# G021old.net
KiCad netlist of a schematic drawn in EAGLE
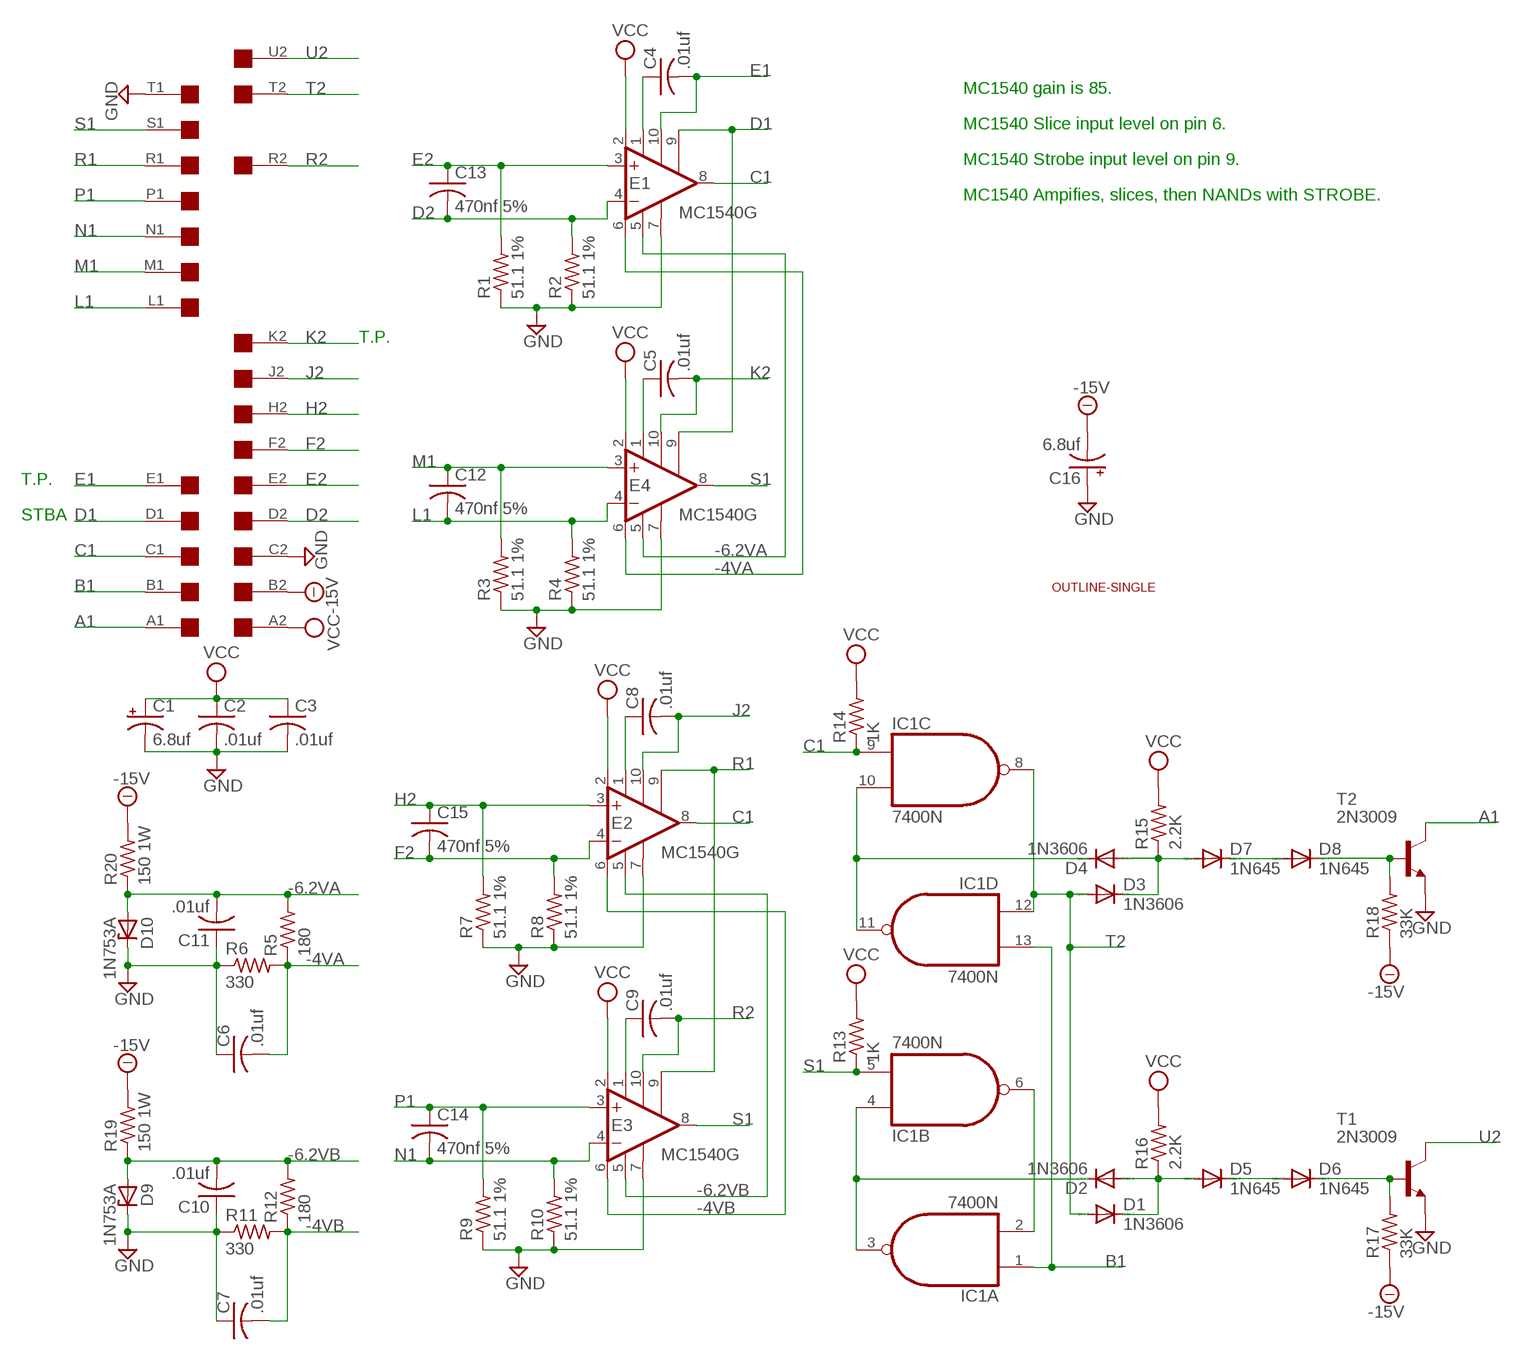
[diagram p0: schematic, sheet 1]

(export (version "E")
  (design (tool "Eeschema 10.0.6"))
  (components
    (comp (ref "C1")
      (value "6.8uf")
      (footprint "eagle-import:E15-5")
      (libsource (lib "eagle-import") (part "CPOL-USE15-5AXIAL"))
    )
    (comp (ref "C2")
      (value ".01uf")
      (footprint "eagle-import:C050-025X075")
      (libsource (lib "eagle-import") (part "C-US050-025X075"))
    )
    (comp (ref "C3")
      (value ".01uf")
      (footprint "eagle-import:C050-025X075")
      (libsource (lib "eagle-import") (part "C-US050-025X075"))
    )
    (comp (ref "C4")
      (value ".01uf")
      (footprint "eagle-import:C050-025X075")
      (libsource (lib "eagle-import") (part "C-US050-025X075"))
    )
    (comp (ref "C5")
      (value ".01uf")
      (footprint "eagle-import:C050-025X075")
      (libsource (lib "eagle-import") (part "C-US050-025X075"))
    )
    (comp (ref "C6")
      (value ".01uf")
      (footprint "eagle-import:C050-025X075")
      (libsource (lib "eagle-import") (part "C-US050-025X075"))
    )
    (comp (ref "C7")
      (value ".01uf")
      (footprint "eagle-import:C050-025X075")
      (libsource (lib "eagle-import") (part "C-US050-025X075"))
    )
    (comp (ref "C8")
      (value ".01uf")
      (footprint "eagle-import:C050-025X075")
      (libsource (lib "eagle-import") (part "C-US050-025X075"))
    )
    (comp (ref "C9")
      (value ".01uf")
      (footprint "eagle-import:C050-025X075")
      (libsource (lib "eagle-import") (part "C-US050-025X075"))
    )
    (comp (ref "C10")
      (value ".01uf")
      (footprint "eagle-import:C050-025X075")
      (libsource (lib "eagle-import") (part "C-US050-025X075"))
    )
    (comp (ref "C11")
      (value ".01uf")
      (footprint "eagle-import:C050-025X075")
      (libsource (lib "eagle-import") (part "C-US050-025X075"))
    )
    (comp (ref "C12")
      (value "470nf 5%")
      (footprint "eagle-import:C050-025X075")
      (libsource (lib "eagle-import") (part "C-US050-025X075"))
    )
    (comp (ref "C13")
      (value "470nf 5%")
      (footprint "eagle-import:C050-025X075")
      (libsource (lib "eagle-import") (part "C-US050-025X075"))
    )
    (comp (ref "C14")
      (value "470nf 5%")
      (footprint "eagle-import:C050-025X075")
      (libsource (lib "eagle-import") (part "C-US050-025X075"))
    )
    (comp (ref "C15")
      (value "470nf 5%")
      (footprint "eagle-import:C050-025X075")
      (libsource (lib "eagle-import") (part "C-US050-025X075"))
    )
    (comp (ref "C16")
      (value "6.8uf")
      (footprint "eagle-import:E15-5")
      (libsource (lib "eagle-import") (part "CPOL-USE15-5AXIAL"))
    )
    (comp (ref "D1")
      (value "1N3606")
      (footprint "eagle-import:DO35-10")
      (libsource (lib "eagle-import") (part "1N4148DO35-10"))
    )
    (comp (ref "D2")
      (value "1N3606")
      (footprint "eagle-import:DO35-10")
      (libsource (lib "eagle-import") (part "1N4148DO35-10"))
    )
    (comp (ref "D3")
      (value "1N3606")
      (footprint "eagle-import:DO35-10")
      (libsource (lib "eagle-import") (part "1N4148DO35-10"))
    )
    (comp (ref "D4")
      (value "1N3606")
      (footprint "eagle-import:DO35-10")
      (libsource (lib "eagle-import") (part "1N4148DO35-10"))
    )
    (comp (ref "D5")
      (value "1N645")
      (footprint "eagle-import:DO35-10")
      (libsource (lib "eagle-import") (part "1N4148DO35-10"))
    )
    (comp (ref "D6")
      (value "1N645")
      (footprint "eagle-import:DO35-10")
      (libsource (lib "eagle-import") (part "1N4148DO35-10"))
    )
    (comp (ref "D7")
      (value "1N645")
      (footprint "eagle-import:DO35-10")
      (libsource (lib "eagle-import") (part "1N4148DO35-10"))
    )
    (comp (ref "D8")
      (value "1N645")
      (footprint "eagle-import:DO35-10")
      (libsource (lib "eagle-import") (part "1N4148DO35-10"))
    )
    (comp (ref "D9")
      (value "1N753A")
      (footprint "eagle-import:F126Z10")
      (libsource (lib "eagle-import") (part "ZENER-DIODEF126-10"))
    )
    (comp (ref "D10")
      (value "1N753A")
      (footprint "eagle-import:F126Z10")
      (libsource (lib "eagle-import") (part "ZENER-DIODEF126-10"))
    )
    (comp (ref "E1")
      (value "MC1540G")
      (footprint "eagle-import:602B")
      (libsource (lib "eagle-import") (part "MC1540G"))
    )
    (comp (ref "E2")
      (value "MC1540G")
      (footprint "eagle-import:602B")
      (libsource (lib "eagle-import") (part "MC1540G"))
    )
    (comp (ref "E3")
      (value "MC1540G")
      (footprint "eagle-import:602B")
      (libsource (lib "eagle-import") (part "MC1540G"))
    )
    (comp (ref "E4")
      (value "MC1540G")
      (footprint "eagle-import:602B")
      (libsource (lib "eagle-import") (part "MC1540G"))
    )
    (comp (ref "IC1")
      (value "7400N")
      (footprint "eagle-import:DIL14")
      (libsource (lib "eagle-import") (part "7400N"))
    )
    (comp (ref "R1")
      (value "51.1 1%")
      (footprint "eagle-import:0207_10")
      (libsource (lib "eagle-import") (part "R-US_0207/10"))
    )
    (comp (ref "R2")
      (value "51.1 1%")
      (footprint "eagle-import:0207_10")
      (libsource (lib "eagle-import") (part "R-US_0207/10"))
    )
    (comp (ref "R3")
      (value "51.1 1%")
      (footprint "eagle-import:0207_10")
      (libsource (lib "eagle-import") (part "R-US_0207/10"))
    )
    (comp (ref "R4")
      (value "51.1 1%")
      (footprint "eagle-import:0207_10")
      (libsource (lib "eagle-import") (part "R-US_0207/10"))
    )
    (comp (ref "R5")
      (value "180")
      (footprint "eagle-import:0207_10")
      (libsource (lib "eagle-import") (part "R-US_0207/10"))
    )
    (comp (ref "R6")
      (value "330")
      (footprint "eagle-import:0207_10")
      (libsource (lib "eagle-import") (part "R-US_0207/10"))
    )
    (comp (ref "R7")
      (value "51.1 1%")
      (footprint "eagle-import:0207_10")
      (libsource (lib "eagle-import") (part "R-US_0207/10"))
    )
    (comp (ref "R8")
      (value "51.1 1%")
      (footprint "eagle-import:0207_10")
      (libsource (lib "eagle-import") (part "R-US_0207/10"))
    )
    (comp (ref "R9")
      (value "51.1 1%")
      (footprint "eagle-import:0207_10")
      (libsource (lib "eagle-import") (part "R-US_0207/10"))
    )
    (comp (ref "R10")
      (value "51.1 1%")
      (footprint "eagle-import:0207_10")
      (libsource (lib "eagle-import") (part "R-US_0207/10"))
    )
    (comp (ref "R11")
      (value "330")
      (footprint "eagle-import:0207_10")
      (libsource (lib "eagle-import") (part "R-US_0207/10"))
    )
    (comp (ref "R12")
      (value "180")
      (footprint "eagle-import:0207_10")
      (libsource (lib "eagle-import") (part "R-US_0207/10"))
    )
    (comp (ref "R13")
      (value "1K")
      (footprint "eagle-import:0207_10")
      (libsource (lib "eagle-import") (part "R-US_0207/10"))
    )
    (comp (ref "R14")
      (value "1K")
      (footprint "eagle-import:0207_10")
      (libsource (lib "eagle-import") (part "R-US_0207/10"))
    )
    (comp (ref "R15")
      (value "2.2K")
      (footprint "eagle-import:0207_10")
      (libsource (lib "eagle-import") (part "R-US_0207/10"))
    )
    (comp (ref "R16")
      (value "2.2K")
      (footprint "eagle-import:0207_10")
      (libsource (lib "eagle-import") (part "R-US_0207/10"))
    )
    (comp (ref "R17")
      (value "33K")
      (footprint "eagle-import:0207_10")
      (libsource (lib "eagle-import") (part "R-US_0207/10"))
    )
    (comp (ref "R18")
      (value "33K")
      (footprint "eagle-import:0207_10")
      (libsource (lib "eagle-import") (part "R-US_0207/10"))
    )
    (comp (ref "R19")
      (value "150 1W")
      (footprint "eagle-import:0414_15")
      (libsource (lib "eagle-import") (part "R-US_0414/15"))
    )
    (comp (ref "R20")
      (value "150 1W")
      (footprint "eagle-import:0414_15")
      (libsource (lib "eagle-import") (part "R-US_0414/15"))
    )
    (comp (ref "T1")
      (value "2N3009")
      (footprint "eagle-import:TO92")
      (libsource (lib "eagle-import") (part "2N3565"))
    )
    (comp (ref "T2")
      (value "2N3009")
      (footprint "eagle-import:TO92")
      (libsource (lib "eagle-import") (part "2N3565"))
    )
    (comp (ref "U$1")
      (value "SINGLE")
      (footprint "eagle-import:EDGE-CON2")
      (libsource (lib "eagle-import") (part "SINGLE"))
    )
    (comp (ref "U$2")
      (value "OUTLINE-SINGLE")
      (footprint "eagle-import:SINGLE")
      (libsource (lib "eagle-import") (part "OUTLINE-SINGLE"))
    )
  )
  (nets
    (net (code "1") (name "-15V") (class "Default")
      (node (ref "C16") (pin "-") (pinfunction "-_-") (pintype "passive"))
      (node (ref "R17") (pin "1") (pinfunction "1_1") (pintype "passive"))
      (node (ref "R18") (pin "1") (pinfunction "1_1") (pintype "passive"))
      (node (ref "R19") (pin "2") (pinfunction "2_2") (pintype "passive"))
      (node (ref "R20") (pin "2") (pinfunction "2_2") (pintype "passive"))
      (node (ref "U$1") (pin "B2") (pinfunction "1_B2") (pintype "bidirectional"))
    )
    (net (code "2") (name "/-4VA") (class "Default")
      (node (ref "C6") (pin "2") (pinfunction "2_2") (pintype "passive"))
      (node (ref "E1") (pin "6") (pinfunction "SLICE_6") (pintype "bidirectional"))
      (node (ref "E4") (pin "6") (pinfunction "SLICE_6") (pintype "bidirectional"))
      (node (ref "R5") (pin "1") (pinfunction "1_1") (pintype "passive"))
      (node (ref "R6") (pin "2") (pinfunction "2_2") (pintype "passive"))
    )
    (net (code "3") (name "/-4VB") (class "Default")
      (node (ref "C7") (pin "2") (pinfunction "2_2") (pintype "passive"))
      (node (ref "E2") (pin "6") (pinfunction "SLICE_6") (pintype "bidirectional"))
      (node (ref "E3") (pin "6") (pinfunction "SLICE_6") (pintype "bidirectional"))
      (node (ref "R11") (pin "2") (pinfunction "2_2") (pintype "passive"))
      (node (ref "R12") (pin "1") (pinfunction "1_1") (pintype "passive"))
    )
    (net (code "4") (name "/-6.2VA") (class "Default")
      (node (ref "C11") (pin "2") (pinfunction "2_2") (pintype "passive"))
      (node (ref "D10") (pin "A") (pinfunction "A_A") (pintype "passive"))
      (node (ref "E1") (pin "5") (pinfunction "V-_5") (pintype "power_in"))
      (node (ref "E4") (pin "5") (pinfunction "V-_5") (pintype "power_in"))
      (node (ref "R20") (pin "1") (pinfunction "1_1") (pintype "passive"))
      (node (ref "R5") (pin "2") (pinfunction "2_2") (pintype "passive"))
    )
    (net (code "5") (name "/-6.2VB") (class "Default")
      (node (ref "C10") (pin "2") (pinfunction "2_2") (pintype "passive"))
      (node (ref "D9") (pin "A") (pinfunction "A_A") (pintype "passive"))
      (node (ref "E2") (pin "5") (pinfunction "V-_5") (pintype "power_in"))
      (node (ref "E3") (pin "5") (pinfunction "V-_5") (pintype "power_in"))
      (node (ref "R12") (pin "2") (pinfunction "2_2") (pintype "passive"))
      (node (ref "R19") (pin "1") (pinfunction "1_1") (pintype "passive"))
    )
    (net (code "6") (name "/A1") (class "Default")
      (node (ref "T2") (pin "1") (pinfunction "C_1") (pintype "passive"))
      (node (ref "U$1") (pin "A1") (pinfunction "1_A1") (pintype "bidirectional"))
    )
    (net (code "7") (name "/B1") (class "Default")
      (node (ref "IC1") (pin "1") (pinfunction "I0_1") (pintype "input"))
      (node (ref "IC1") (pin "13") (pinfunction "I1_13") (pintype "input"))
      (node (ref "U$1") (pin "B1") (pinfunction "1_B1") (pintype "bidirectional"))
    )
    (net (code "8") (name "/C1") (class "Default")
      (node (ref "E1") (pin "8") (pinfunction "OUT_8") (pintype "open_collector"))
      (node (ref "E2") (pin "8") (pinfunction "OUT_8") (pintype "open_collector"))
      (node (ref "IC1") (pin "9") (pinfunction "I0_9") (pintype "input"))
      (node (ref "R14") (pin "1") (pinfunction "1_1") (pintype "passive"))
      (node (ref "U$1") (pin "C1") (pinfunction "1_C1") (pintype "bidirectional"))
    )
    (net (code "9") (name "/D1") (class "Default")
      (node (ref "E1") (pin "9") (pinfunction "ISTROBE_9") (pintype "passive"))
      (node (ref "E4") (pin "9") (pinfunction "ISTROBE_9") (pintype "passive"))
      (node (ref "U$1") (pin "D1") (pinfunction "1_D1") (pintype "bidirectional"))
    )
    (net (code "10") (name "/D2") (class "Default")
      (node (ref "C13") (pin "2") (pinfunction "2_2") (pintype "passive"))
      (node (ref "E1") (pin "4") (pinfunction "-IN_4") (pintype "input"))
      (node (ref "R2") (pin "2") (pinfunction "2_2") (pintype "passive"))
      (node (ref "U$1") (pin "D2") (pinfunction "1_D2") (pintype "bidirectional"))
    )
    (net (code "11") (name "/E1") (class "Default")
      (node (ref "C4") (pin "2") (pinfunction "2_2") (pintype "passive"))
      (node (ref "E1") (pin "10") (pinfunction "CEXTB_10") (pintype "passive"))
      (node (ref "U$1") (pin "E1") (pinfunction "1_E1") (pintype "bidirectional"))
    )
    (net (code "12") (name "/E2") (class "Default")
      (node (ref "C13") (pin "1") (pinfunction "1_1") (pintype "passive"))
      (node (ref "E1") (pin "3") (pinfunction "+IN_3") (pintype "input"))
      (node (ref "R1") (pin "2") (pinfunction "2_2") (pintype "passive"))
      (node (ref "U$1") (pin "E2") (pinfunction "1_E2") (pintype "bidirectional"))
    )
    (net (code "13") (name "/F2") (class "Default")
      (node (ref "C15") (pin "2") (pinfunction "2_2") (pintype "passive"))
      (node (ref "E2") (pin "4") (pinfunction "-IN_4") (pintype "input"))
      (node (ref "R8") (pin "2") (pinfunction "2_2") (pintype "passive"))
      (node (ref "U$1") (pin "F2") (pinfunction "1_F2") (pintype "bidirectional"))
    )
    (net (code "14") (name "/H2") (class "Default")
      (node (ref "C15") (pin "1") (pinfunction "1_1") (pintype "passive"))
      (node (ref "E2") (pin "3") (pinfunction "+IN_3") (pintype "input"))
      (node (ref "R7") (pin "2") (pinfunction "2_2") (pintype "passive"))
      (node (ref "U$1") (pin "H2") (pinfunction "1_H2") (pintype "bidirectional"))
    )
    (net (code "15") (name "/J2") (class "Default")
      (node (ref "C8") (pin "2") (pinfunction "2_2") (pintype "passive"))
      (node (ref "E2") (pin "10") (pinfunction "CEXTB_10") (pintype "passive"))
      (node (ref "U$1") (pin "J2") (pinfunction "1_J2") (pintype "bidirectional"))
    )
    (net (code "16") (name "/K2") (class "Default")
      (node (ref "C5") (pin "2") (pinfunction "2_2") (pintype "passive"))
      (node (ref "E4") (pin "10") (pinfunction "CEXTB_10") (pintype "passive"))
      (node (ref "U$1") (pin "K2") (pinfunction "1_K2") (pintype "bidirectional"))
    )
    (net (code "17") (name "/L1") (class "Default")
      (node (ref "C12") (pin "2") (pinfunction "2_2") (pintype "passive"))
      (node (ref "E4") (pin "4") (pinfunction "-IN_4") (pintype "input"))
      (node (ref "R4") (pin "2") (pinfunction "2_2") (pintype "passive"))
      (node (ref "U$1") (pin "L1") (pinfunction "1_L1") (pintype "bidirectional"))
    )
    (net (code "18") (name "/M1") (class "Default")
      (node (ref "C12") (pin "1") (pinfunction "1_1") (pintype "passive"))
      (node (ref "E4") (pin "3") (pinfunction "+IN_3") (pintype "input"))
      (node (ref "R3") (pin "2") (pinfunction "2_2") (pintype "passive"))
      (node (ref "U$1") (pin "M1") (pinfunction "1_M1") (pintype "bidirectional"))
    )
    (net (code "19") (name "/N1") (class "Default")
      (node (ref "C14") (pin "2") (pinfunction "2_2") (pintype "passive"))
      (node (ref "E3") (pin "4") (pinfunction "-IN_4") (pintype "input"))
      (node (ref "R10") (pin "2") (pinfunction "2_2") (pintype "passive"))
      (node (ref "U$1") (pin "N1") (pinfunction "1_N1") (pintype "bidirectional"))
    )
    (net (code "20") (name "/P1") (class "Default")
      (node (ref "C14") (pin "1") (pinfunction "1_1") (pintype "passive"))
      (node (ref "E3") (pin "3") (pinfunction "+IN_3") (pintype "input"))
      (node (ref "R9") (pin "2") (pinfunction "2_2") (pintype "passive"))
      (node (ref "U$1") (pin "P1") (pinfunction "1_P1") (pintype "bidirectional"))
    )
    (net (code "21") (name "/R1") (class "Default")
      (node (ref "E2") (pin "9") (pinfunction "ISTROBE_9") (pintype "passive"))
      (node (ref "E3") (pin "9") (pinfunction "ISTROBE_9") (pintype "passive"))
      (node (ref "U$1") (pin "R1") (pinfunction "1_R1") (pintype "bidirectional"))
    )
    (net (code "22") (name "/R2") (class "Default")
      (node (ref "C9") (pin "2") (pinfunction "2_2") (pintype "passive"))
      (node (ref "E3") (pin "10") (pinfunction "CEXTB_10") (pintype "passive"))
      (node (ref "U$1") (pin "R2") (pinfunction "1_R2") (pintype "bidirectional"))
    )
    (net (code "23") (name "/S1") (class "Default")
      (node (ref "E3") (pin "8") (pinfunction "OUT_8") (pintype "open_collector"))
      (node (ref "E4") (pin "8") (pinfunction "OUT_8") (pintype "open_collector"))
      (node (ref "IC1") (pin "5") (pinfunction "I1_5") (pintype "input"))
      (node (ref "R13") (pin "1") (pinfunction "1_1") (pintype "passive"))
      (node (ref "U$1") (pin "S1") (pinfunction "1_S1") (pintype "bidirectional"))
    )
    (net (code "24") (name "/T2") (class "Default")
      (node (ref "D1") (pin "A") (pinfunction "A_A") (pintype "passive"))
      (node (ref "D3") (pin "A") (pinfunction "A_A") (pintype "passive"))
      (node (ref "IC1") (pin "12") (pinfunction "I0_12") (pintype "input"))
      (node (ref "IC1") (pin "8") (pinfunction "O_8") (pintype "output"))
      (node (ref "U$1") (pin "T2") (pinfunction "1_T2") (pintype "bidirectional"))
    )
    (net (code "25") (name "/U2") (class "Default")
      (node (ref "T1") (pin "1") (pinfunction "C_1") (pintype "passive"))
      (node (ref "U$1") (pin "U2") (pinfunction "1_U2") (pintype "bidirectional"))
    )
    (net (code "26") (name "GND") (class "Default")
      (node (ref "C1") (pin "-") (pinfunction "-_-") (pintype "passive"))
      (node (ref "C10") (pin "1") (pinfunction "1_1") (pintype "passive"))
      (node (ref "C11") (pin "1") (pinfunction "1_1") (pintype "passive"))
      (node (ref "C16") (pin "+") (pinfunction "+_+") (pintype "passive"))
      (node (ref "C2") (pin "2") (pinfunction "2_2") (pintype "passive"))
      (node (ref "C3") (pin "2") (pinfunction "2_2") (pintype "passive"))
      (node (ref "C6") (pin "1") (pinfunction "1_1") (pintype "passive"))
      (node (ref "C7") (pin "1") (pinfunction "1_1") (pintype "passive"))
      (node (ref "D10") (pin "C") (pinfunction "C_C") (pintype "passive"))
      (node (ref "D9") (pin "C") (pinfunction "C_C") (pintype "passive"))
      (node (ref "E1") (pin "7") (pinfunction "GND_7") (pintype "power_in"))
      (node (ref "E2") (pin "7") (pinfunction "GND_7") (pintype "power_in"))
      (node (ref "E3") (pin "7") (pinfunction "GND_7") (pintype "power_in"))
      (node (ref "E4") (pin "7") (pinfunction "GND_7") (pintype "power_in"))
      (node (ref "R1") (pin "1") (pinfunction "1_1") (pintype "passive"))
      (node (ref "R10") (pin "1") (pinfunction "1_1") (pintype "passive"))
      (node (ref "R11") (pin "1") (pinfunction "1_1") (pintype "passive"))
      (node (ref "R2") (pin "1") (pinfunction "1_1") (pintype "passive"))
      (node (ref "R3") (pin "1") (pinfunction "1_1") (pintype "passive"))
      (node (ref "R4") (pin "1") (pinfunction "1_1") (pintype "passive"))
      (node (ref "R6") (pin "1") (pinfunction "1_1") (pintype "passive"))
      (node (ref "R7") (pin "1") (pinfunction "1_1") (pintype "passive"))
      (node (ref "R8") (pin "1") (pinfunction "1_1") (pintype "passive"))
      (node (ref "R9") (pin "1") (pinfunction "1_1") (pintype "passive"))
      (node (ref "T1") (pin "3") (pinfunction "E_3") (pintype "passive"))
      (node (ref "T2") (pin "3") (pinfunction "E_3") (pintype "passive"))
      (node (ref "U$1") (pin "C2") (pinfunction "1_C2") (pintype "bidirectional"))
      (node (ref "U$1") (pin "T1") (pinfunction "1_T1") (pintype "bidirectional"))
    )
    (net (code "27") (name "Net-(D1-PadC)") (class "Default")
      (node (ref "D1") (pin "C") (pinfunction "C_C") (pintype "passive"))
      (node (ref "D2") (pin "A") (pinfunction "A_A") (pintype "passive"))
      (node (ref "D5") (pin "A") (pinfunction "A_A") (pintype "passive"))
      (node (ref "R16") (pin "1") (pinfunction "1_1") (pintype "passive"))
    )
    (net (code "28") (name "Net-(D3-PadC)") (class "Default")
      (node (ref "D3") (pin "C") (pinfunction "C_C") (pintype "passive"))
      (node (ref "D4") (pin "A") (pinfunction "A_A") (pintype "passive"))
      (node (ref "D7") (pin "A") (pinfunction "A_A") (pintype "passive"))
      (node (ref "R15") (pin "1") (pinfunction "1_1") (pintype "passive"))
    )
    (net (code "29") (name "Net-(D5-PadC)") (class "Default")
      (node (ref "D5") (pin "C") (pinfunction "C_C") (pintype "passive"))
      (node (ref "D6") (pin "A") (pinfunction "A_A") (pintype "passive"))
    )
    (net (code "30") (name "Net-(D7-PadC)") (class "Default")
      (node (ref "D7") (pin "C") (pinfunction "C_C") (pintype "passive"))
      (node (ref "D8") (pin "A") (pinfunction "A_A") (pintype "passive"))
    )
    (net (code "31") (name "Net-(E1-CEXTA)") (class "Default")
      (node (ref "C4") (pin "1") (pinfunction "1_1") (pintype "passive"))
      (node (ref "E1") (pin "1") (pinfunction "CEXTA_1") (pintype "passive"))
    )
    (net (code "32") (name "Net-(E2-CEXTA)") (class "Default")
      (node (ref "C8") (pin "1") (pinfunction "1_1") (pintype "passive"))
      (node (ref "E2") (pin "1") (pinfunction "CEXTA_1") (pintype "passive"))
    )
    (net (code "33") (name "Net-(E3-CEXTA)") (class "Default")
      (node (ref "C9") (pin "1") (pinfunction "1_1") (pintype "passive"))
      (node (ref "E3") (pin "1") (pinfunction "CEXTA_1") (pintype "passive"))
    )
    (net (code "34") (name "Net-(E4-CEXTA)") (class "Default")
      (node (ref "C5") (pin "1") (pinfunction "1_1") (pintype "passive"))
      (node (ref "E4") (pin "1") (pinfunction "CEXTA_1") (pintype "passive"))
    )
    (net (code "35") (name "Net-(IC1A-I1)") (class "Default")
      (node (ref "IC1") (pin "2") (pinfunction "I1_2") (pintype "input"))
      (node (ref "IC1") (pin "6") (pinfunction "O_6") (pintype "output"))
    )
    (net (code "36") (name "Net-(IC1A-O)") (class "Default")
      (node (ref "D2") (pin "C") (pinfunction "C_C") (pintype "passive"))
      (node (ref "IC1") (pin "3") (pinfunction "O_3") (pintype "output"))
      (node (ref "IC1") (pin "4") (pinfunction "I0_4") (pintype "input"))
    )
    (net (code "37") (name "Net-(IC1C-I1)") (class "Default")
      (node (ref "D4") (pin "C") (pinfunction "C_C") (pintype "passive"))
      (node (ref "IC1") (pin "10") (pinfunction "I1_10") (pintype "input"))
      (node (ref "IC1") (pin "11") (pinfunction "O_11") (pintype "output"))
    )
    (net (code "38") (name "Net-(T1-B)") (class "Default")
      (node (ref "D6") (pin "C") (pinfunction "C_C") (pintype "passive"))
      (node (ref "R17") (pin "2") (pinfunction "2_2") (pintype "passive"))
      (node (ref "T1") (pin "2") (pinfunction "B_2") (pintype "passive"))
    )
    (net (code "39") (name "Net-(T2-B)") (class "Default")
      (node (ref "D8") (pin "C") (pinfunction "C_C") (pintype "passive"))
      (node (ref "R18") (pin "2") (pinfunction "2_2") (pintype "passive"))
      (node (ref "T2") (pin "2") (pinfunction "B_2") (pintype "passive"))
    )
    (net (code "40") (name "VCC") (class "Default")
      (node (ref "C1") (pin "+") (pinfunction "+_+") (pintype "passive"))
      (node (ref "C2") (pin "1") (pinfunction "1_1") (pintype "passive"))
      (node (ref "C3") (pin "1") (pinfunction "1_1") (pintype "passive"))
      (node (ref "E1") (pin "2") (pinfunction "V+_2") (pintype "power_in"))
      (node (ref "E2") (pin "2") (pinfunction "V+_2") (pintype "power_in"))
      (node (ref "E3") (pin "2") (pinfunction "V+_2") (pintype "power_in"))
      (node (ref "E4") (pin "2") (pinfunction "V+_2") (pintype "power_in"))
      (node (ref "R13") (pin "2") (pinfunction "2_2") (pintype "passive"))
      (node (ref "R14") (pin "2") (pinfunction "2_2") (pintype "passive"))
      (node (ref "R15") (pin "2") (pinfunction "2_2") (pintype "passive"))
      (node (ref "R16") (pin "2") (pinfunction "2_2") (pintype "passive"))
      (node (ref "U$1") (pin "A2") (pinfunction "1_A2") (pintype "bidirectional"))
    )
  )
)
